# touch.net
KiCad netlist of a schematic drawn in EAGLE
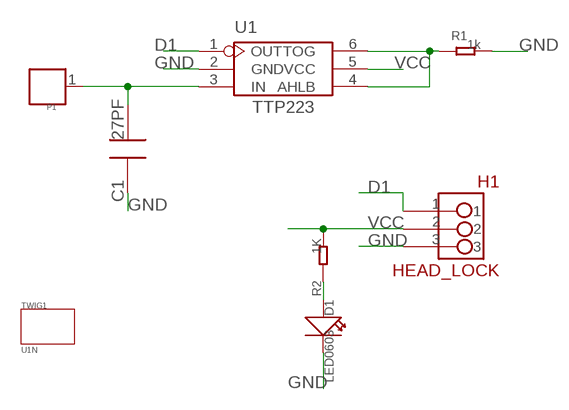
[diagram p0: schematic, sheet 1]

(export (version "E")
  (design (tool "Eeschema 10.0.6"))
  (components
    (comp (ref "C1")
      (value "27PF")
      (footprint "eagle-import:0603")
      (libsource (lib "eagle-import") (part "C0603"))
    )
    (comp (ref "D1")
      (value "LED0603")
      (footprint "eagle-import:LED0603")
      (libsource (lib "eagle-import") (part "LED0603"))
    )
    (comp (ref "H1")
      (value "HEAD_LOCK")
      (footprint "eagle-import:HEAD_LOCK")
      (libsource (lib "eagle-import") (part "HEAD_LOCK"))
    )
    (comp (ref "P1")
      (value "PAD'D450MIL'")
      (footprint "eagle-import:1P-D450")
      (libsource (lib "eagle-import") (part "PAD'D450MIL'"))
    )
    (comp (ref "R1")
      (value "1k")
      (footprint "eagle-import:0603")
      (libsource (lib "eagle-import") (part "R0603"))
    )
    (comp (ref "R2")
      (value "1K")
      (footprint "eagle-import:0603")
      (libsource (lib "eagle-import") (part "R0603"))
    )
    (comp (ref "TWIG1")
      (value "U1N")
      (footprint "eagle-import:U1N")
      (libsource (lib "eagle-import") (part "U1N"))
    )
    (comp (ref "U1")
      (value "TTP223")
      (footprint "eagle-import:SOT23-6L")
      (libsource (lib "eagle-import") (part "TTP223"))
    )
  )
  (nets
    (net (code "1") (name "/D1") (class "Default")
      (node (ref "H1") (pin "1") (pinfunction "1_1") (pintype "passive"))
      (node (ref "U1") (pin "1") (pinfunction "OUT_1") (pintype "bidirectional"))
    )
    (net (code "2") (name "/GND") (class "Default")
      (node (ref "C1") (pin "1") (pinfunction "1_1") (pintype "bidirectional"))
      (node (ref "D1") (pin "2") (pinfunction "-_2") (pintype "bidirectional"))
      (node (ref "H1") (pin "3") (pinfunction "3_3") (pintype "passive"))
      (node (ref "R1") (pin "2") (pinfunction "2_2") (pintype "bidirectional"))
      (node (ref "U1") (pin "2") (pinfunction "GND_2") (pintype "bidirectional"))
    )
    (net (code "3") (name "/VCC") (class "Default")
      (node (ref "H1") (pin "2") (pinfunction "2_2") (pintype "passive"))
      (node (ref "R2") (pin "2") (pinfunction "2_2") (pintype "bidirectional"))
      (node (ref "U1") (pin "5") (pinfunction "VCC_5") (pintype "bidirectional"))
    )
    (net (code "4") (name "Net-(D1-+)") (class "Default")
      (node (ref "D1") (pin "1") (pinfunction "+_1") (pintype "bidirectional"))
      (node (ref "R2") (pin "1") (pinfunction "1_1") (pintype "bidirectional"))
    )
    (net (code "5") (name "Net-(P1-P$1)") (class "Default")
      (node (ref "C1") (pin "2") (pinfunction "2_2") (pintype "bidirectional"))
      (node (ref "P1") (pin "1") (pinfunction "P$1_1") (pintype "bidirectional"))
      (node (ref "U1") (pin "3") (pinfunction "IN_3") (pintype "bidirectional"))
    )
    (net (code "6") (name "Net-(U1-AHLB)") (class "Default")
      (node (ref "R1") (pin "1") (pinfunction "1_1") (pintype "bidirectional"))
      (node (ref "U1") (pin "4") (pinfunction "AHLB_4") (pintype "bidirectional"))
      (node (ref "U1") (pin "6") (pinfunction "TOG_6") (pintype "bidirectional"))
    )
  )
)
